# Gilbert_Cell_Mixer.net
KiCad netlist of a schematic drawn in EAGLE
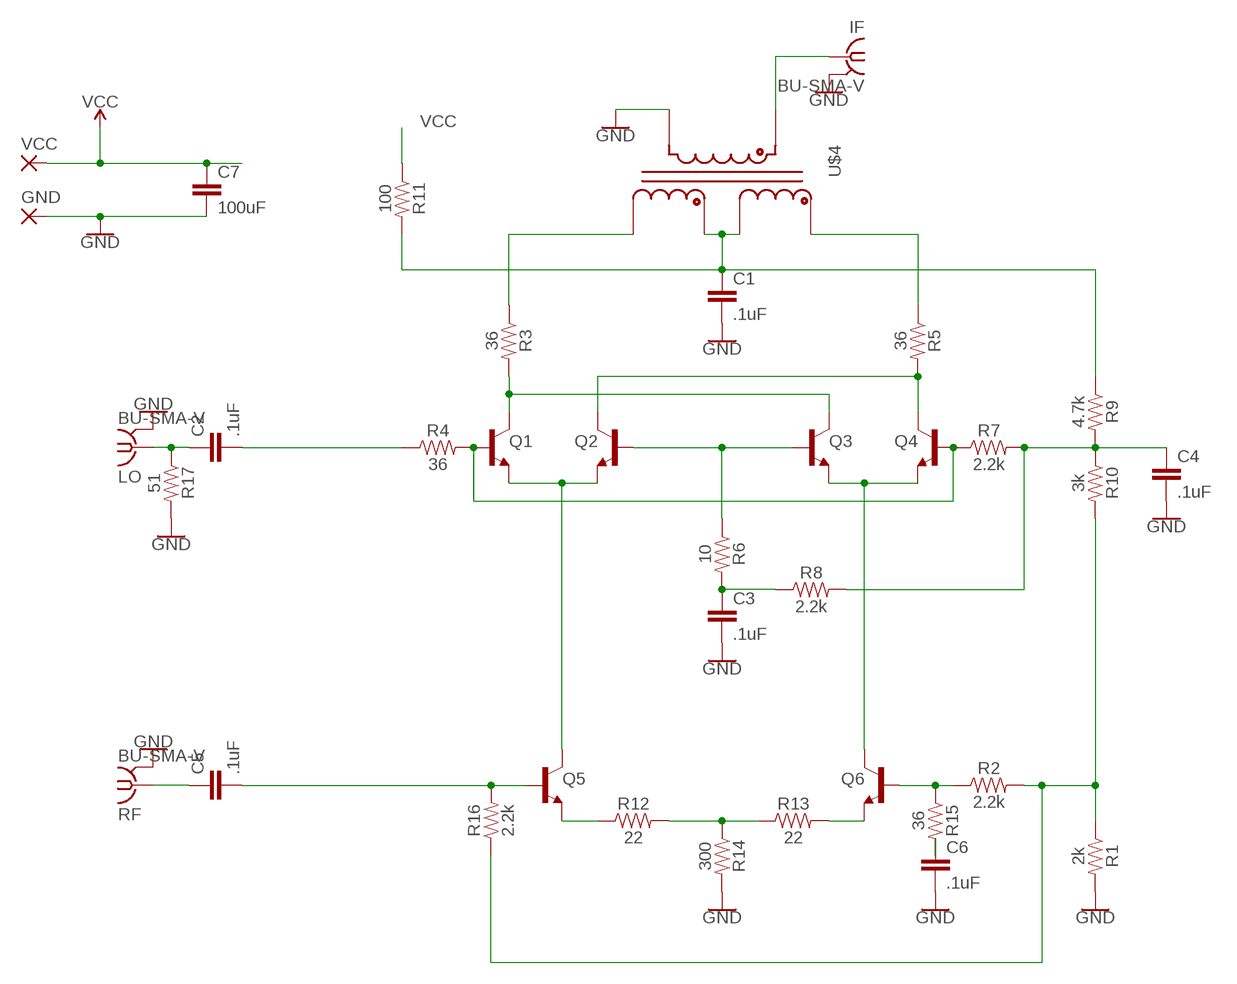
[diagram p0: schematic, sheet 1]

(export (version "E")
  (design (tool "Eeschema 10.0.6"))
  (components
    (comp (ref "C1")
      (value ".1uF")
      (footprint "eagle-import:C5B3.5")
      (libsource (lib "eagle-import") (part "C5/3.5"))
    )
    (comp (ref "C2")
      (value ".1uF")
      (footprint "eagle-import:C5B3.5")
      (libsource (lib "eagle-import") (part "C5/3.5"))
    )
    (comp (ref "C3")
      (value ".1uF")
      (footprint "eagle-import:C5B3.5")
      (libsource (lib "eagle-import") (part "C5/3.5"))
    )
    (comp (ref "C4")
      (value ".1uF")
      (footprint "eagle-import:C5B3.5")
      (libsource (lib "eagle-import") (part "C5/3.5"))
    )
    (comp (ref "C5")
      (value ".1uF")
      (footprint "eagle-import:C5B3.5")
      (libsource (lib "eagle-import") (part "C5/3.5"))
    )
    (comp (ref "C6")
      (value ".1uF")
      (footprint "eagle-import:C5B3.5")
      (libsource (lib "eagle-import") (part "C5/3.5"))
    )
    (comp (ref "C7")
      (value "100uF")
      (footprint "eagle-import:C5B3.5")
      (libsource (lib "eagle-import") (part "C5/3.5"))
    )
    (comp (ref "GND")
      (value "3,17/1,1")
      (footprint "eagle-import:3,17_1,1")
      (libsource (lib "eagle-import") (part "3,17/1,1"))
    )
    (comp (ref "IF")
      (value "BU-SMA-V")
      (footprint "eagle-import:BU-SMA-V")
      (libsource (lib "eagle-import") (part "BU-SMA-V"))
    )
    (comp (ref "LO")
      (value "BU-SMA-V")
      (footprint "eagle-import:BU-SMA-V")
      (libsource (lib "eagle-import") (part "BU-SMA-V"))
    )
    (comp (ref "Q1")
      (value "TRANS_NPN-2N3904")
      (footprint "eagle-import:TO-92")
      (libsource (lib "eagle-import") (part "TRANS_NPN-2N3904"))
    )
    (comp (ref "Q2")
      (value "TRANS_NPN-2N3904")
      (footprint "eagle-import:TO-92")
      (libsource (lib "eagle-import") (part "TRANS_NPN-2N3904"))
    )
    (comp (ref "Q3")
      (value "TRANS_NPN-2N3904")
      (footprint "eagle-import:TO-92")
      (libsource (lib "eagle-import") (part "TRANS_NPN-2N3904"))
    )
    (comp (ref "Q4")
      (value "TRANS_NPN-2N3904")
      (footprint "eagle-import:TO-92")
      (libsource (lib "eagle-import") (part "TRANS_NPN-2N3904"))
    )
    (comp (ref "Q5")
      (value "TRANS_NPN-2N3904")
      (footprint "eagle-import:TO-92")
      (libsource (lib "eagle-import") (part "TRANS_NPN-2N3904"))
    )
    (comp (ref "Q6")
      (value "TRANS_NPN-2N3904")
      (footprint "eagle-import:TO-92")
      (libsource (lib "eagle-import") (part "TRANS_NPN-2N3904"))
    )
    (comp (ref "R1")
      (value "2k")
      (footprint "eagle-import:AXIAL-0.3")
      (libsource (lib "eagle-import") (part "1KOHM-HORIZ-1/4W-1%"))
    )
    (comp (ref "R2")
      (value "2.2k")
      (footprint "eagle-import:AXIAL-0.3")
      (libsource (lib "eagle-import") (part "1KOHM-HORIZ-1/4W-1%"))
    )
    (comp (ref "R3")
      (value "36")
      (footprint "eagle-import:AXIAL-0.3")
      (libsource (lib "eagle-import") (part "1KOHM-HORIZ-1/4W-1%"))
    )
    (comp (ref "R4")
      (value "36")
      (footprint "eagle-import:AXIAL-0.3")
      (libsource (lib "eagle-import") (part "1KOHM-HORIZ-1/4W-1%"))
    )
    (comp (ref "R5")
      (value "36")
      (footprint "eagle-import:AXIAL-0.3")
      (libsource (lib "eagle-import") (part "1KOHM-HORIZ-1/4W-1%"))
    )
    (comp (ref "R6")
      (value "10")
      (footprint "eagle-import:AXIAL-0.3")
      (libsource (lib "eagle-import") (part "1KOHM-HORIZ-1/4W-1%"))
    )
    (comp (ref "R7")
      (value "2.2k")
      (footprint "eagle-import:AXIAL-0.3")
      (libsource (lib "eagle-import") (part "1KOHM-HORIZ-1/4W-1%"))
    )
    (comp (ref "R8")
      (value "2.2k")
      (footprint "eagle-import:AXIAL-0.3")
      (libsource (lib "eagle-import") (part "1KOHM-HORIZ-1/4W-1%"))
    )
    (comp (ref "R9")
      (value "4.7k")
      (footprint "eagle-import:AXIAL-0.3")
      (libsource (lib "eagle-import") (part "1KOHM-HORIZ-1/4W-1%"))
    )
    (comp (ref "R10")
      (value "3k")
      (footprint "eagle-import:AXIAL-0.3")
      (libsource (lib "eagle-import") (part "1KOHM-HORIZ-1/4W-1%"))
    )
    (comp (ref "R11")
      (value "100")
      (footprint "eagle-import:AXIAL-0.3")
      (libsource (lib "eagle-import") (part "1KOHM-HORIZ-1/4W-1%"))
    )
    (comp (ref "R12")
      (value "22")
      (footprint "eagle-import:AXIAL-0.3")
      (libsource (lib "eagle-import") (part "1KOHM-HORIZ-1/4W-1%"))
    )
    (comp (ref "R13")
      (value "22")
      (footprint "eagle-import:AXIAL-0.3")
      (libsource (lib "eagle-import") (part "1KOHM-HORIZ-1/4W-1%"))
    )
    (comp (ref "R14")
      (value "300")
      (footprint "eagle-import:AXIAL-0.3")
      (libsource (lib "eagle-import") (part "1KOHM-HORIZ-1/4W-1%"))
    )
    (comp (ref "R15")
      (value "36")
      (footprint "eagle-import:AXIAL-0.3")
      (libsource (lib "eagle-import") (part "1KOHM-HORIZ-1/4W-1%"))
    )
    (comp (ref "R16")
      (value "2.2k")
      (footprint "eagle-import:AXIAL-0.3")
      (libsource (lib "eagle-import") (part "1KOHM-HORIZ-1/4W-1%"))
    )
    (comp (ref "R17")
      (value "51")
      (footprint "eagle-import:AXIAL-0.3")
      (libsource (lib "eagle-import") (part "1KOHM-HORIZ-1/4W-1%"))
    )
    (comp (ref "RF")
      (value "BU-SMA-V")
      (footprint "eagle-import:BU-SMA-V")
      (libsource (lib "eagle-import") (part "BU-SMA-V"))
    )
    (comp (ref "U$4")
      (value "T50_SPLITTER")
      (footprint "eagle-import:T50_SPLITTER")
      (libsource (lib "eagle-import") (part "T50_SPLITTER"))
    )
    (comp (ref "VCC")
      (value "3,17/1,1")
      (footprint "eagle-import:3,17_1,1")
      (libsource (lib "eagle-import") (part "3,17/1,1"))
    )
  )
  (nets
    (net (code "1") (name "GND") (class "Default")
      (node (ref "C1") (pin "2") (pinfunction "2_2") (pintype "passive"))
      (node (ref "C3") (pin "2") (pinfunction "2_2") (pintype "passive"))
      (node (ref "C4") (pin "2") (pinfunction "2_2") (pintype "passive"))
      (node (ref "C6") (pin "2") (pinfunction "2_2") (pintype "passive"))
      (node (ref "C7") (pin "2") (pinfunction "2_2") (pintype "passive"))
      (node (ref "GND") (pin "1") (pinfunction "P_1") (pintype "passive"))
      (node (ref "IF") (pin "2") (pinfunction "2_2") (pintype "passive"))
      (node (ref "IF") (pin "3") (pinfunction "2_3") (pintype "passive"))
      (node (ref "IF") (pin "4") (pinfunction "2_4") (pintype "passive"))
      (node (ref "IF") (pin "5") (pinfunction "2_5") (pintype "passive"))
      (node (ref "LO") (pin "2") (pinfunction "2_2") (pintype "passive"))
      (node (ref "LO") (pin "3") (pinfunction "2_3") (pintype "passive"))
      (node (ref "LO") (pin "4") (pinfunction "2_4") (pintype "passive"))
      (node (ref "LO") (pin "5") (pinfunction "2_5") (pintype "passive"))
      (node (ref "R1") (pin "P$2") (pinfunction "2_P$2") (pintype "passive"))
      (node (ref "R14") (pin "P$2") (pinfunction "2_P$2") (pintype "passive"))
      (node (ref "R17") (pin "P$2") (pinfunction "2_P$2") (pintype "passive"))
      (node (ref "RF") (pin "2") (pinfunction "2_2") (pintype "passive"))
      (node (ref "RF") (pin "3") (pinfunction "2_3") (pintype "passive"))
      (node (ref "RF") (pin "4") (pinfunction "2_4") (pintype "passive"))
      (node (ref "RF") (pin "5") (pinfunction "2_5") (pintype "passive"))
      (node (ref "U$4") (pin "C1A") (pinfunction "C1A_C1A") (pintype "bidirectional"))
    )
    (net (code "2") (name "Net-(C5-Pad1)") (class "Default")
      (node (ref "C5") (pin "1") (pinfunction "1_1") (pintype "passive"))
      (node (ref "RF") (pin "1") (pinfunction "1_1") (pintype "passive"))
    )
    (net (code "3") (name "Net-(IF-Pad1)") (class "Default")
      (node (ref "IF") (pin "1") (pinfunction "1_1") (pintype "passive"))
      (node (ref "U$4") (pin "C1B") (pinfunction "C1B_C1B") (pintype "bidirectional"))
    )
    (net (code "4") (name "Net-(Q1-B)") (class "Default")
      (node (ref "Q1") (pin "2") (pinfunction "B_2") (pintype "passive"))
      (node (ref "Q4") (pin "2") (pinfunction "B_2") (pintype "passive"))
      (node (ref "R4") (pin "P$2") (pinfunction "2_P$2") (pintype "passive"))
      (node (ref "R7") (pin "P$1") (pinfunction "1_P$1") (pintype "passive"))
    )
    (net (code "5") (name "Net-(Q1-C)") (class "Default")
      (node (ref "Q1") (pin "3") (pinfunction "C_3") (pintype "passive"))
      (node (ref "Q3") (pin "3") (pinfunction "C_3") (pintype "passive"))
      (node (ref "R3") (pin "P$2") (pinfunction "2_P$2") (pintype "passive"))
    )
    (net (code "6") (name "Net-(Q1-E)") (class "Default")
      (node (ref "Q1") (pin "1") (pinfunction "E_1") (pintype "passive"))
      (node (ref "Q2") (pin "1") (pinfunction "E_1") (pintype "passive"))
      (node (ref "Q5") (pin "3") (pinfunction "C_3") (pintype "passive"))
    )
    (net (code "7") (name "Net-(Q2-B)") (class "Default")
      (node (ref "Q2") (pin "2") (pinfunction "B_2") (pintype "passive"))
      (node (ref "Q3") (pin "2") (pinfunction "B_2") (pintype "passive"))
      (node (ref "R6") (pin "P$1") (pinfunction "1_P$1") (pintype "passive"))
    )
    (net (code "8") (name "Net-(Q2-C)") (class "Default")
      (node (ref "Q2") (pin "3") (pinfunction "C_3") (pintype "passive"))
      (node (ref "Q4") (pin "3") (pinfunction "C_3") (pintype "passive"))
      (node (ref "R5") (pin "P$2") (pinfunction "2_P$2") (pintype "passive"))
    )
    (net (code "9") (name "Net-(Q3-E)") (class "Default")
      (node (ref "Q3") (pin "1") (pinfunction "E_1") (pintype "passive"))
      (node (ref "Q4") (pin "1") (pinfunction "E_1") (pintype "passive"))
      (node (ref "Q6") (pin "3") (pinfunction "C_3") (pintype "passive"))
    )
    (net (code "10") (name "Net-(Q5-B)") (class "Default")
      (node (ref "C5") (pin "2") (pinfunction "2_2") (pintype "passive"))
      (node (ref "Q5") (pin "2") (pinfunction "B_2") (pintype "passive"))
      (node (ref "R16") (pin "P$2") (pinfunction "2_P$2") (pintype "passive"))
    )
    (net (code "11") (name "Net-(Q5-E)") (class "Default")
      (node (ref "Q5") (pin "1") (pinfunction "E_1") (pintype "passive"))
      (node (ref "R12") (pin "P$1") (pinfunction "1_P$1") (pintype "passive"))
    )
    (net (code "12") (name "Net-(Q6-B)") (class "Default")
      (node (ref "Q6") (pin "2") (pinfunction "B_2") (pintype "passive"))
      (node (ref "R15") (pin "P$1") (pinfunction "1_P$1") (pintype "passive"))
      (node (ref "R2") (pin "P$1") (pinfunction "1_P$1") (pintype "passive"))
    )
    (net (code "13") (name "Net-(Q6-E)") (class "Default")
      (node (ref "Q6") (pin "1") (pinfunction "E_1") (pintype "passive"))
      (node (ref "R13") (pin "P$2") (pinfunction "2_P$2") (pintype "passive"))
    )
    (net (code "14") (name "Net-(R1-1)") (class "Default")
      (node (ref "R1") (pin "P$1") (pinfunction "1_P$1") (pintype "passive"))
      (node (ref "R10") (pin "P$2") (pinfunction "2_P$2") (pintype "passive"))
      (node (ref "R16") (pin "P$1") (pinfunction "1_P$1") (pintype "passive"))
      (node (ref "R2") (pin "P$2") (pinfunction "2_P$2") (pintype "passive"))
    )
    (net (code "15") (name "Net-(R3-1)") (class "Default")
      (node (ref "R3") (pin "P$1") (pinfunction "1_P$1") (pintype "passive"))
      (node (ref "U$4") (pin "C2B") (pinfunction "C3A_C2B") (pintype "bidirectional"))
    )
    (net (code "16") (name "Net-(R4-1)") (class "Default")
      (node (ref "C2") (pin "2") (pinfunction "2_2") (pintype "passive"))
      (node (ref "R4") (pin "P$1") (pinfunction "1_P$1") (pintype "passive"))
    )
    (net (code "17") (name "Net-(R5-1)") (class "Default")
      (node (ref "R5") (pin "P$1") (pinfunction "1_P$1") (pintype "passive"))
      (node (ref "U$4") (pin "C3B") (pinfunction "C2B_C3B") (pintype "bidirectional"))
    )
    (net (code "18") (name "Net-(R6-2)") (class "Default")
      (node (ref "C3") (pin "1") (pinfunction "1_1") (pintype "passive"))
      (node (ref "R6") (pin "P$2") (pinfunction "2_P$2") (pintype "passive"))
      (node (ref "R8") (pin "P$1") (pinfunction "1_P$1") (pintype "passive"))
    )
    (net (code "19") (name "Net-(R10-1)") (class "Default")
      (node (ref "C4") (pin "1") (pinfunction "1_1") (pintype "passive"))
      (node (ref "R10") (pin "P$1") (pinfunction "1_P$1") (pintype "passive"))
      (node (ref "R7") (pin "P$2") (pinfunction "2_P$2") (pintype "passive"))
      (node (ref "R8") (pin "P$2") (pinfunction "2_P$2") (pintype "passive"))
      (node (ref "R9") (pin "P$2") (pinfunction "2_P$2") (pintype "passive"))
    )
    (net (code "20") (name "Net-(R11-2)") (class "Default")
      (node (ref "C1") (pin "1") (pinfunction "1_1") (pintype "passive"))
      (node (ref "R11") (pin "P$2") (pinfunction "2_P$2") (pintype "passive"))
      (node (ref "R9") (pin "P$1") (pinfunction "1_P$1") (pintype "passive"))
      (node (ref "U$4") (pin "C2A") (pinfunction "C3B_C2A") (pintype "bidirectional"))
      (node (ref "U$4") (pin "C3A") (pinfunction "C2A_C3A") (pintype "bidirectional"))
    )
    (net (code "21") (name "Net-(R12-2)") (class "Default")
      (node (ref "R12") (pin "P$2") (pinfunction "2_P$2") (pintype "passive"))
      (node (ref "R13") (pin "P$1") (pinfunction "1_P$1") (pintype "passive"))
      (node (ref "R14") (pin "P$1") (pinfunction "1_P$1") (pintype "passive"))
    )
    (net (code "22") (name "Net-(R15-2)") (class "Default")
      (node (ref "C6") (pin "1") (pinfunction "1_1") (pintype "passive"))
      (node (ref "R15") (pin "P$2") (pinfunction "2_P$2") (pintype "passive"))
    )
    (net (code "23") (name "Net-(R17-1)") (class "Default")
      (node (ref "C2") (pin "1") (pinfunction "1_1") (pintype "passive"))
      (node (ref "LO") (pin "1") (pinfunction "1_1") (pintype "passive"))
      (node (ref "R17") (pin "P$1") (pinfunction "1_P$1") (pintype "passive"))
    )
    (net (code "24") (name "VCC") (class "Default")
      (node (ref "C7") (pin "1") (pinfunction "1_1") (pintype "passive"))
      (node (ref "R11") (pin "P$1") (pinfunction "1_P$1") (pintype "passive"))
      (node (ref "VCC") (pin "1") (pinfunction "P_1") (pintype "passive"))
    )
  )
)
